# pll.net
KiCad netlist of a schematic drawn in Altium Designer
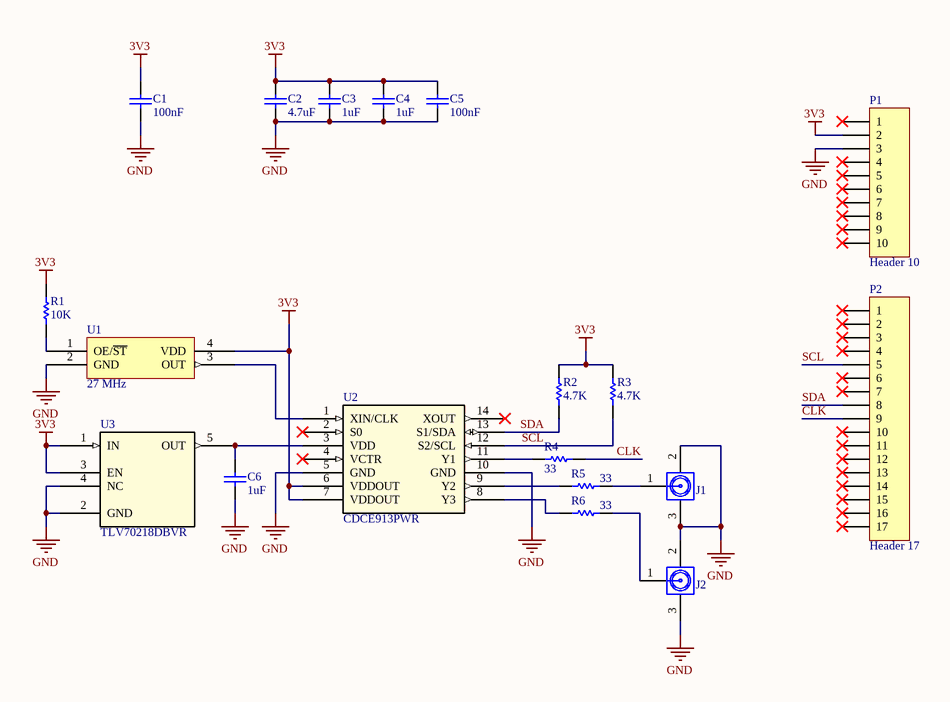
[diagram p0: pll.SchDoc]

(export (version "E")
  (design (tool "Eeschema 10.0.6"))
  (components
    (comp (ref "C1")
      (value "100nF")
      (footprint "CAP_0603")
      (description "Multilayer Ceramic Capacitors")
      (fields (field (name "TOLERANCE") "10%") (field (name "Comment") "MLCC"))
      (libsource (lib "Capacitors") (part "MLCC"))
    )
    (comp (ref "C2")
      (value "4.7uF")
      (footprint "CAP_0603")
      (description "Multilayer Ceramic Capacitors")
      (fields (field (name "TOLERANCE") "10%") (field (name "Comment") "MLCC"))
      (libsource (lib "Capacitors") (part "MLCC"))
    )
    (comp (ref "C3")
      (value "1uF")
      (footprint "CAP_0603")
      (description "Multilayer Ceramic Capacitors")
      (fields (field (name "TOLERANCE") "10%") (field (name "Comment") "MLCC"))
      (libsource (lib "Capacitors") (part "MLCC"))
    )
    (comp (ref "C4")
      (value "1uF")
      (footprint "CAP_0603")
      (description "Multilayer Ceramic Capacitors")
      (fields (field (name "TOLERANCE") "10%") (field (name "Comment") "MLCC"))
      (libsource (lib "Capacitors") (part "MLCC"))
    )
    (comp (ref "C5")
      (value "100nF")
      (footprint "CAP_0603")
      (description "Multilayer Ceramic Capacitors")
      (fields (field (name "TOLERANCE") "10%") (field (name "Comment") "MLCC"))
      (libsource (lib "Capacitors") (part "MLCC"))
    )
    (comp (ref "C6")
      (value "1uF")
      (footprint "CAP_0603")
      (description "Multilayer Ceramic Capacitors")
      (fields (field (name "TOLERANCE") "10%") (field (name "Comment") "MLCC"))
      (libsource (lib "Capacitors") (part "MLCC"))
    )
    (comp (ref "J1")
      (value "RF Connector")
      (footprint "RF CONNECTOR (1)")
      (description "VAO ITEM, MINI RF HEADER")
      (libsource (lib "Connectors") (part "RF Connector"))
    )
    (comp (ref "J2")
      (value "RF Connector")
      (footprint "RF CONNECTOR (1)")
      (description "VAO ITEM, MINI RF HEADER")
      (libsource (lib "Connectors") (part "RF Connector"))
    )
    (comp (ref "P1")
      (value "Header 10")
      (footprint "HDR1X10")
      (description "Header, 10-Pin")
      (fields (field (name "PUBLISHER") "Altium Limited"))
      (libsource (lib "Miscellaneous Connectors") (part "Header 10"))
    )
    (comp (ref "P2")
      (value "Header 17")
      (footprint "HDR1X17")
      (description "Header, 17-Pin")
      (fields (field (name "PUBLISHER") "Altium Limited"))
      (libsource (lib "Miscellaneous Connectors") (part "Header 17"))
    )
    (comp (ref "R1")
      (value "10K")
      (footprint "RC0603N")
      (description "Chip Resistors")
      (fields (field (name "Comment") "RES"))
      (libsource (lib "Resistors") (part "RES"))
    )
    (comp (ref "R2")
      (value "4.7K")
      (footprint "RC0603N")
      (description "Chip Resistors")
      (fields (field (name "Comment") "RES"))
      (libsource (lib "Resistors") (part "RES"))
    )
    (comp (ref "R3")
      (value "4.7K")
      (footprint "RC0603N")
      (description "Chip Resistors")
      (fields (field (name "Comment") "RES"))
      (libsource (lib "Resistors") (part "RES"))
    )
    (comp (ref "R4")
      (value "33")
      (footprint "RC0603N")
      (description "Chip Resistors")
      (fields (field (name "Comment") "RES"))
      (libsource (lib "Resistors") (part "RES"))
    )
    (comp (ref "R5")
      (value "33")
      (footprint "RC0603N")
      (description "Chip Resistors")
      (fields (field (name "Comment") "RES"))
      (libsource (lib "Resistors") (part "RES"))
    )
    (comp (ref "R6")
      (value "33")
      (footprint "RC0603N")
      (description "Chip Resistors")
      (fields (field (name "Comment") "RES"))
      (libsource (lib "Resistors") (part "RES"))
    )
    (comp (ref "U1")
      (value "XO")
      (footprint "QFN_3225_4P")
      (description "SiTime Ultra Performance Oscillator")
      (fields (field (name "MANUFACTURER") "SiTime") (field (name "FREQUENCY") "27 MHz"))
      (libsource (lib "Crystals") (part "XO"))
    )
    (comp (ref "U2")
      (value "CDCE913")
      (footprint "PW14")
      (description "CDCE(L)913: Flexible Low Power LVCMOS Clock Generator With SSC Support for EMI Reduction")
      (fields
        (field (name "MANUFACTURER") "Texas Instruments")
        (field (name "MANUFACTURER_PART_NUMBER") "CDCE913PWR")
        (field (name "COPYRIGHT") "Copyright (C) 2018 Accelerated Designs. All rights reserved")
      )
      (libsource (lib "TI") (part "CDCE913"))
    )
    (comp (ref "U3")
      (value "TLV70218DBVR")
      (footprint "DBV5")
      (description "TLV702 300-mA, Low-IQ, Low-Dropout Regulator")
      (fields
        (field (name "MANUFACTURER") "Texas Instruments")
        (field (name "MANUFACTURER_PART_NUMBER") "TLV70212DBVR")
        (field (name "COPYRIGHT") "Copyright (C) 2020 MWLabs. All rights reserved")
      )
      (libsource (lib "TI") (part "TLV702"))
    )
  )
  (nets
    (net (code "1") (name "/CLK") (class "Default")
      (node (ref "P2") (pin "9") (pinfunction "9_9") (pintype "passive"))
      (node (ref "R4") (pin "1") (pinfunction "1_1") (pintype "passive"))
    )
    (net (code "2") (name "/SCL") (class "Default")
      (node (ref "P2") (pin "5") (pinfunction "5_5") (pintype "passive"))
      (node (ref "R3") (pin "1") (pinfunction "1_1") (pintype "passive"))
      (node (ref "U2") (pin "12") (pinfunction "S2/SCL_12") (pintype "input"))
    )
    (net (code "3") (name "/SDA") (class "Default")
      (node (ref "P2") (pin "8") (pinfunction "8_8") (pintype "passive"))
      (node (ref "R2") (pin "1") (pinfunction "1_1") (pintype "passive"))
      (node (ref "U2") (pin "13") (pinfunction "S1/SDA_13") (pintype "bidirectional"))
    )
    (net (code "4") (name "3V3") (class "Default")
      (node (ref "C1") (pin "2") (pinfunction "2_2") (pintype "passive"))
      (node (ref "C2") (pin "2") (pinfunction "2_2") (pintype "passive"))
      (node (ref "C3") (pin "2") (pinfunction "2_2") (pintype "passive"))
      (node (ref "C4") (pin "2") (pinfunction "2_2") (pintype "passive"))
      (node (ref "C5") (pin "2") (pinfunction "2_2") (pintype "passive"))
      (node (ref "P1") (pin "2") (pinfunction "2_2") (pintype "passive"))
      (node (ref "R1") (pin "2") (pinfunction "2_2") (pintype "passive"))
      (node (ref "R2") (pin "2") (pinfunction "2_2") (pintype "passive"))
      (node (ref "R3") (pin "2") (pinfunction "2_2") (pintype "passive"))
      (node (ref "U1") (pin "4") (pinfunction "VDD_4") (pintype "power_in"))
      (node (ref "U2") (pin "6") (pinfunction "VDDOUT_6") (pintype "power_in"))
      (node (ref "U2") (pin "7") (pinfunction "VDDOUT_7") (pintype "power_in"))
      (node (ref "U3") (pin "1") (pinfunction "IN_1") (pintype "input"))
      (node (ref "U3") (pin "3") (pinfunction "EN_3") (pintype "passive"))
    )
    (net (code "5") (name "GND") (class "Default")
      (node (ref "C1") (pin "1") (pinfunction "1_1") (pintype "passive"))
      (node (ref "C2") (pin "1") (pinfunction "1_1") (pintype "passive"))
      (node (ref "C3") (pin "1") (pinfunction "1_1") (pintype "passive"))
      (node (ref "C4") (pin "1") (pinfunction "1_1") (pintype "passive"))
      (node (ref "C5") (pin "1") (pinfunction "1_1") (pintype "passive"))
      (node (ref "C6") (pin "1") (pinfunction "1_1") (pintype "passive"))
      (node (ref "J1") (pin "2") (pinfunction "GND_2") (pintype "passive"))
      (node (ref "J1") (pin "3") (pinfunction "GND_3") (pintype "passive"))
      (node (ref "J2") (pin "2") (pinfunction "GND_2") (pintype "passive"))
      (node (ref "J2") (pin "3") (pinfunction "GND_3") (pintype "passive"))
      (node (ref "P1") (pin "3") (pinfunction "3_3") (pintype "passive"))
      (node (ref "U1") (pin "2") (pinfunction "GND_2") (pintype "passive"))
      (node (ref "U2") (pin "10") (pinfunction "GND_10") (pintype "power_in"))
      (node (ref "U2") (pin "5") (pinfunction "GND_5") (pintype "power_in"))
      (node (ref "U3") (pin "2") (pinfunction "GND_2") (pintype "power_in"))
      (node (ref "U3") (pin "4") (pinfunction "NC_4") (pintype "passive"))
    )
    (net (code "6") (name "Net-(J1-SIG)") (class "Default")
      (node (ref "J1") (pin "1") (pinfunction "SIG_1") (pintype "passive"))
      (node (ref "R5") (pin "1") (pinfunction "1_1") (pintype "passive"))
    )
    (net (code "7") (name "Net-(J2-SIG)") (class "Default")
      (node (ref "J2") (pin "1") (pinfunction "SIG_1") (pintype "passive"))
      (node (ref "R6") (pin "1") (pinfunction "1_1") (pintype "passive"))
    )
    (net (code "8") (name "Net-(U1-OE{slash}~{ST})") (class "Default")
      (node (ref "R1") (pin "1") (pinfunction "1_1") (pintype "passive"))
      (node (ref "U1") (pin "1") (pinfunction "OE/~{ST}_1") (pintype "passive"))
    )
    (net (code "9") (name "Net-(U1-OUT)") (class "Default")
      (node (ref "U1") (pin "3") (pinfunction "OUT_3") (pintype "output"))
      (node (ref "U2") (pin "1") (pinfunction "XIN/CLK_1") (pintype "input"))
    )
    (net (code "10") (name "Net-(U2-VDD)") (class "Default")
      (node (ref "C6") (pin "2") (pinfunction "2_2") (pintype "passive"))
      (node (ref "U2") (pin "3") (pinfunction "VDD_3") (pintype "power_in"))
      (node (ref "U3") (pin "5") (pinfunction "OUT_5") (pintype "output"))
    )
    (net (code "11") (name "Net-(U2-Y1)") (class "Default")
      (node (ref "R4") (pin "2") (pinfunction "2_2") (pintype "passive"))
      (node (ref "U2") (pin "11") (pinfunction "Y1_11") (pintype "output"))
    )
    (net (code "12") (name "Net-(U2-Y2)") (class "Default")
      (node (ref "R5") (pin "2") (pinfunction "2_2") (pintype "passive"))
      (node (ref "U2") (pin "9") (pinfunction "Y2_9") (pintype "output"))
    )
    (net (code "13") (name "Net-(U2-Y3)") (class "Default")
      (node (ref "R6") (pin "2") (pinfunction "2_2") (pintype "passive"))
      (node (ref "U2") (pin "8") (pinfunction "Y3_8") (pintype "output"))
    )
    (net (code "14") (name "unconnected-(P1-Pad1)") (class "Default")
      (node (ref "P1") (pin "1") (pinfunction "1_1") (pintype "passive+no_connect"))
    )
    (net (code "15") (name "unconnected-(P1-Pad4)") (class "Default")
      (node (ref "P1") (pin "4") (pinfunction "4_4") (pintype "passive+no_connect"))
    )
    (net (code "16") (name "unconnected-(P1-Pad5)") (class "Default")
      (node (ref "P1") (pin "5") (pinfunction "5_5") (pintype "passive+no_connect"))
    )
    (net (code "17") (name "unconnected-(P1-Pad6)") (class "Default")
      (node (ref "P1") (pin "6") (pinfunction "6_6") (pintype "passive+no_connect"))
    )
    (net (code "18") (name "unconnected-(P1-Pad7)") (class "Default")
      (node (ref "P1") (pin "7") (pinfunction "7_7") (pintype "passive+no_connect"))
    )
    (net (code "19") (name "unconnected-(P1-Pad8)") (class "Default")
      (node (ref "P1") (pin "8") (pinfunction "8_8") (pintype "passive+no_connect"))
    )
    (net (code "20") (name "unconnected-(P1-Pad9)") (class "Default")
      (node (ref "P1") (pin "9") (pinfunction "9_9") (pintype "passive+no_connect"))
    )
    (net (code "21") (name "unconnected-(P1-Pad10)") (class "Default")
      (node (ref "P1") (pin "10") (pinfunction "10_10") (pintype "passive+no_connect"))
    )
    (net (code "22") (name "unconnected-(P2-Pad1)") (class "Default")
      (node (ref "P2") (pin "1") (pinfunction "1_1") (pintype "passive+no_connect"))
    )
    (net (code "23") (name "unconnected-(P2-Pad2)") (class "Default")
      (node (ref "P2") (pin "2") (pinfunction "2_2") (pintype "passive+no_connect"))
    )
    (net (code "24") (name "unconnected-(P2-Pad3)") (class "Default")
      (node (ref "P2") (pin "3") (pinfunction "3_3") (pintype "passive+no_connect"))
    )
    (net (code "25") (name "unconnected-(P2-Pad4)") (class "Default")
      (node (ref "P2") (pin "4") (pinfunction "4_4") (pintype "passive+no_connect"))
    )
    (net (code "26") (name "unconnected-(P2-Pad6)") (class "Default")
      (node (ref "P2") (pin "6") (pinfunction "6_6") (pintype "passive+no_connect"))
    )
    (net (code "27") (name "unconnected-(P2-Pad7)") (class "Default")
      (node (ref "P2") (pin "7") (pinfunction "7_7") (pintype "passive+no_connect"))
    )
    (net (code "28") (name "unconnected-(P2-Pad10)") (class "Default")
      (node (ref "P2") (pin "10") (pinfunction "10_10") (pintype "passive+no_connect"))
    )
    (net (code "29") (name "unconnected-(P2-Pad11)") (class "Default")
      (node (ref "P2") (pin "11") (pinfunction "11_11") (pintype "passive+no_connect"))
    )
    (net (code "30") (name "unconnected-(P2-Pad12)") (class "Default")
      (node (ref "P2") (pin "12") (pinfunction "12_12") (pintype "passive+no_connect"))
    )
    (net (code "31") (name "unconnected-(P2-Pad13)") (class "Default")
      (node (ref "P2") (pin "13") (pinfunction "13_13") (pintype "passive+no_connect"))
    )
    (net (code "32") (name "unconnected-(P2-Pad14)") (class "Default")
      (node (ref "P2") (pin "14") (pinfunction "14_14") (pintype "passive+no_connect"))
    )
    (net (code "33") (name "unconnected-(P2-Pad15)") (class "Default")
      (node (ref "P2") (pin "15") (pinfunction "15_15") (pintype "passive+no_connect"))
    )
    (net (code "34") (name "unconnected-(P2-Pad16)") (class "Default")
      (node (ref "P2") (pin "16") (pinfunction "16_16") (pintype "passive+no_connect"))
    )
    (net (code "35") (name "unconnected-(P2-Pad17)") (class "Default")
      (node (ref "P2") (pin "17") (pinfunction "17_17") (pintype "passive+no_connect"))
    )
    (net (code "36") (name "unconnected-(U2-S0-Pad2)") (class "Default")
      (node (ref "U2") (pin "2") (pinfunction "S0_2") (pintype "input+no_connect"))
    )
    (net (code "37") (name "unconnected-(U2-VCTR-Pad4)") (class "Default")
      (node (ref "U2") (pin "4") (pinfunction "VCTR_4") (pintype "input+no_connect"))
    )
    (net (code "38") (name "unconnected-(U2-XOUT-Pad14)") (class "Default")
      (node (ref "U2") (pin "14") (pinfunction "XOUT_14") (pintype "output+no_connect"))
    )
  )
)
